# Numpad.net
KiCad netlist of a schematic drawn in EAGLE
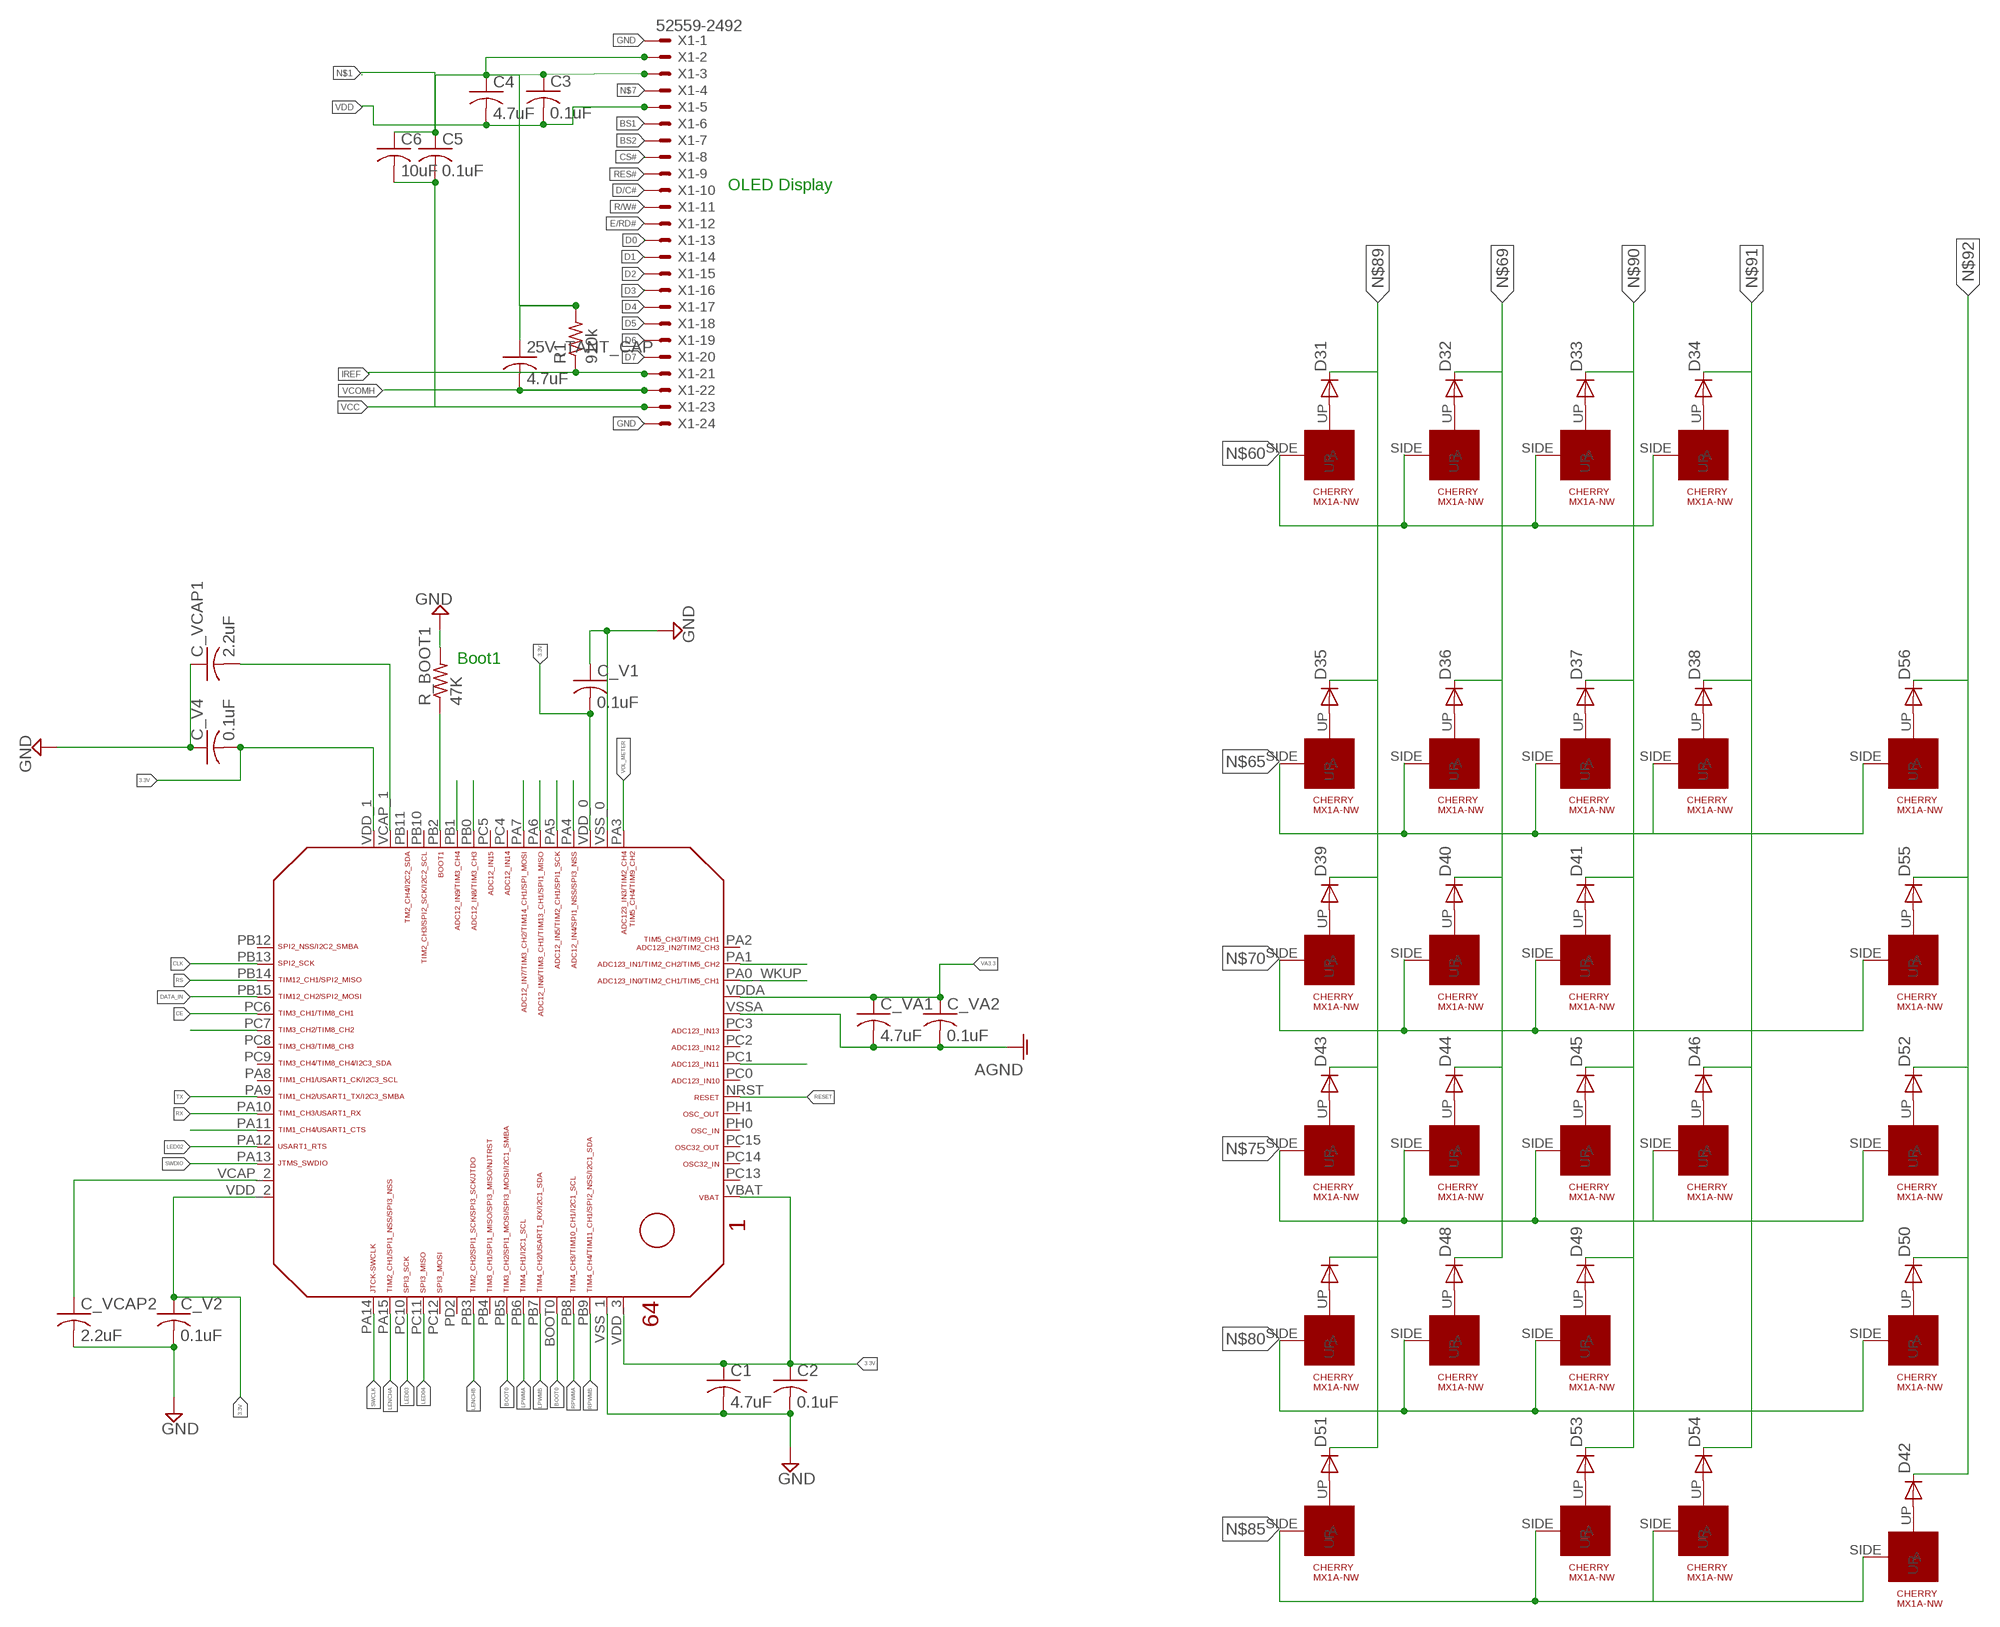
[diagram p0: schematic, sheet 1]

(export (version "E")
  (design (tool "Eeschema 10.0.6"))
  (components
    (comp (ref "25V_TANT_CAP")
      (value "4.7uF")
      (footprint "eagle-import:C0805")
      (libsource (lib "eagle-import") (part "C-USC0805"))
    )
    (comp (ref "C1")
      (value "4.7uF")
      (footprint "eagle-import:C0603")
      (libsource (lib "eagle-import") (part "resistor_348_C-USC0603"))
    )
    (comp (ref "C2")
      (value "0.1uF")
      (footprint "eagle-import:C0603")
      (libsource (lib "eagle-import") (part "resistor_348_C-USC0603"))
    )
    (comp (ref "C3")
      (value "0.1uF")
      (footprint "eagle-import:C0603")
      (libsource (lib "eagle-import") (part "resistor_348_C-USC0603"))
    )
    (comp (ref "C4")
      (value "4.7uF")
      (footprint "eagle-import:C0603")
      (libsource (lib "eagle-import") (part "resistor_348_C-USC0603"))
    )
    (comp (ref "C5")
      (value "0.1uF")
      (footprint "eagle-import:C0603")
      (libsource (lib "eagle-import") (part "resistor_348_C-USC0603"))
    )
    (comp (ref "C6")
      (value "10uF")
      (footprint "eagle-import:C0603")
      (libsource (lib "eagle-import") (part "resistor_348_C-USC0603"))
    )
    (comp (ref "C_V1")
      (value "0.1uF")
      (footprint "eagle-import:C0603")
      (libsource (lib "eagle-import") (part "resistor_348_C-USC0603"))
    )
    (comp (ref "C_V2")
      (value "0.1uF")
      (footprint "eagle-import:C0603")
      (libsource (lib "eagle-import") (part "resistor_348_C-USC0603"))
    )
    (comp (ref "C_V4")
      (value "0.1uF")
      (footprint "eagle-import:C0603")
      (libsource (lib "eagle-import") (part "resistor_348_C-USC0603"))
    )
    (comp (ref "C_VA1")
      (value "4.7uF")
      (footprint "eagle-import:C0603")
      (libsource (lib "eagle-import") (part "resistor_348_C-USC0603"))
    )
    (comp (ref "C_VA2")
      (value "0.1uF")
      (footprint "eagle-import:C0603")
      (libsource (lib "eagle-import") (part "resistor_348_C-USC0603"))
    )
    (comp (ref "C_VCAP1")
      (value "2.2uF")
      (footprint "eagle-import:C0603")
      (libsource (lib "eagle-import") (part "resistor_348_C-USC0603"))
    )
    (comp (ref "C_VCAP2")
      (value "2.2uF")
      (footprint "eagle-import:C0603")
      (libsource (lib "eagle-import") (part "resistor_348_C-USC0603"))
    )
    (comp (ref "D31")
      (value "1N4148DO35-7")
      (footprint "eagle-import:DO35-7")
      (libsource (lib "eagle-import") (part "1N4148DO35-7"))
    )
    (comp (ref "D32")
      (value "1N4148DO35-7")
      (footprint "eagle-import:DO35-7")
      (libsource (lib "eagle-import") (part "1N4148DO35-7"))
    )
    (comp (ref "D33")
      (value "1N4148DO35-7")
      (footprint "eagle-import:DO35-7")
      (libsource (lib "eagle-import") (part "1N4148DO35-7"))
    )
    (comp (ref "D34")
      (value "1N4148DO35-7")
      (footprint "eagle-import:DO35-7")
      (libsource (lib "eagle-import") (part "1N4148DO35-7"))
    )
    (comp (ref "D35")
      (value "1N4148DO35-7")
      (footprint "eagle-import:DO35-7")
      (libsource (lib "eagle-import") (part "1N4148DO35-7"))
    )
    (comp (ref "D36")
      (value "1N4148DO35-7")
      (footprint "eagle-import:DO35-7")
      (libsource (lib "eagle-import") (part "1N4148DO35-7"))
    )
    (comp (ref "D37")
      (value "1N4148DO35-7")
      (footprint "eagle-import:DO35-7")
      (libsource (lib "eagle-import") (part "1N4148DO35-7"))
    )
    (comp (ref "D38")
      (value "1N4148DO35-7")
      (footprint "eagle-import:DO35-7")
      (libsource (lib "eagle-import") (part "1N4148DO35-7"))
    )
    (comp (ref "D39")
      (value "1N4148DO35-7")
      (footprint "eagle-import:DO35-7")
      (libsource (lib "eagle-import") (part "1N4148DO35-7"))
    )
    (comp (ref "D40")
      (value "1N4148DO35-7")
      (footprint "eagle-import:DO35-7")
      (libsource (lib "eagle-import") (part "1N4148DO35-7"))
    )
    (comp (ref "D41")
      (value "1N4148DO35-7")
      (footprint "eagle-import:DO35-7")
      (libsource (lib "eagle-import") (part "1N4148DO35-7"))
    )
    (comp (ref "D42")
      (value "1N4148DO35-7")
      (footprint "eagle-import:DO35-7")
      (libsource (lib "eagle-import") (part "1N4148DO35-7"))
    )
    (comp (ref "D43")
      (value "1N4148DO35-7")
      (footprint "eagle-import:DO35-7")
      (libsource (lib "eagle-import") (part "1N4148DO35-7"))
    )
    (comp (ref "D44")
      (value "1N4148DO35-7")
      (footprint "eagle-import:DO35-7")
      (libsource (lib "eagle-import") (part "1N4148DO35-7"))
    )
    (comp (ref "D45")
      (value "1N4148DO35-7")
      (footprint "eagle-import:DO35-7")
      (libsource (lib "eagle-import") (part "1N4148DO35-7"))
    )
    (comp (ref "D46")
      (value "1N4148DO35-7")
      (footprint "eagle-import:DO35-7")
      (libsource (lib "eagle-import") (part "1N4148DO35-7"))
    )
    (comp (ref "D47")
      (value "1N4148DO35-7")
      (footprint "eagle-import:DO35-7")
      (libsource (lib "eagle-import") (part "1N4148DO35-7"))
    )
    (comp (ref "D48")
      (value "1N4148DO35-7")
      (footprint "eagle-import:DO35-7")
      (libsource (lib "eagle-import") (part "1N4148DO35-7"))
    )
    (comp (ref "D49")
      (value "1N4148DO35-7")
      (footprint "eagle-import:DO35-7")
      (libsource (lib "eagle-import") (part "1N4148DO35-7"))
    )
    (comp (ref "D50")
      (value "1N4148DO35-7")
      (footprint "eagle-import:DO35-7")
      (libsource (lib "eagle-import") (part "1N4148DO35-7"))
    )
    (comp (ref "D51")
      (value "1N4148DO35-7")
      (footprint "eagle-import:DO35-7")
      (libsource (lib "eagle-import") (part "1N4148DO35-7"))
    )
    (comp (ref "D52")
      (value "1N4148DO35-7")
      (footprint "eagle-import:DO35-7")
      (libsource (lib "eagle-import") (part "1N4148DO35-7"))
    )
    (comp (ref "D53")
      (value "1N4148DO35-7")
      (footprint "eagle-import:DO35-7")
      (libsource (lib "eagle-import") (part "1N4148DO35-7"))
    )
    (comp (ref "D54")
      (value "1N4148DO35-7")
      (footprint "eagle-import:DO35-7")
      (libsource (lib "eagle-import") (part "1N4148DO35-7"))
    )
    (comp (ref "D55")
      (value "1N4148DO35-7")
      (footprint "eagle-import:DO35-7")
      (libsource (lib "eagle-import") (part "1N4148DO35-7"))
    )
    (comp (ref "D56")
      (value "1N4148DO35-7")
      (footprint "eagle-import:DO35-7")
      (libsource (lib "eagle-import") (part "1N4148DO35-7"))
    )
    (comp (ref "R1")
      (value "910k")
      (footprint "eagle-import:R0603")
      (libsource (lib "eagle-import") (part "R-US_R0603"))
    )
    (comp (ref "R_BOOT1")
      (value "47K")
      (footprint "eagle-import:R0603")
      (libsource (lib "eagle-import") (part "R-US_R0603"))
    )
    (comp (ref "U$31")
      (value "CHERRY-MX1A-E1NW")
      (footprint "eagle-import:CHERRYMX-NN")
      (libsource (lib "eagle-import") (part "CHERRY-MX1A-E1NW"))
    )
    (comp (ref "U$35")
      (value "STM32F405/415_LQFP64")
      (footprint "eagle-import:STM32F405_415_LQFP64")
      (libsource (lib "eagle-import") (part "STM32F405/415_LQFP64"))
    )
    (comp (ref "U$36")
      (value "CHERRY-MX1A-E1NW")
      (footprint "eagle-import:CHERRYMX-NN")
      (libsource (lib "eagle-import") (part "CHERRY-MX1A-E1NW"))
    )
    (comp (ref "U$37")
      (value "CHERRY-MX1A-E1NW")
      (footprint "eagle-import:CHERRYMX-NN")
      (libsource (lib "eagle-import") (part "CHERRY-MX1A-E1NW"))
    )
    (comp (ref "U$38")
      (value "CHERRY-MX1A-E1NW")
      (footprint "eagle-import:CHERRYMX-NN")
      (libsource (lib "eagle-import") (part "CHERRY-MX1A-E1NW"))
    )
    (comp (ref "U$39")
      (value "CHERRY-MX1A-E1NW")
      (footprint "eagle-import:CHERRYMX-NN")
      (libsource (lib "eagle-import") (part "CHERRY-MX1A-E1NW"))
    )
    (comp (ref "U$40")
      (value "CHERRY-MX1A-E1NW")
      (footprint "eagle-import:CHERRYMX-NN")
      (libsource (lib "eagle-import") (part "CHERRY-MX1A-E1NW"))
    )
    (comp (ref "U$41")
      (value "CHERRY-MX1A-E1NW")
      (footprint "eagle-import:CHERRYMX-NN")
      (libsource (lib "eagle-import") (part "CHERRY-MX1A-E1NW"))
    )
    (comp (ref "U$42")
      (value "CHERRY-MX1A-E1NW")
      (footprint "eagle-import:CHERRYMX-NN")
      (libsource (lib "eagle-import") (part "CHERRY-MX1A-E1NW"))
    )
    (comp (ref "U$43")
      (value "CHERRY-MX1A-E1NW")
      (footprint "eagle-import:CHERRYMX-NN")
      (libsource (lib "eagle-import") (part "CHERRY-MX1A-E1NW"))
    )
    (comp (ref "U$44")
      (value "CHERRY-MX1A-E1NW")
      (footprint "eagle-import:CHERRYMX-NN")
      (libsource (lib "eagle-import") (part "CHERRY-MX1A-E1NW"))
    )
    (comp (ref "U$45")
      (value "CHERRY-MX1A-E1NW")
      (footprint "eagle-import:CHERRYMX-NN")
      (libsource (lib "eagle-import") (part "CHERRY-MX1A-E1NW"))
    )
    (comp (ref "U$46")
      (value "CHERRY-MX1A-E1NW")
      (footprint "eagle-import:CHERRYMX-NN")
      (libsource (lib "eagle-import") (part "CHERRY-MX1A-E1NW"))
    )
    (comp (ref "U$47")
      (value "CHERRY-MX1A-E1NW")
      (footprint "eagle-import:CHERRYMX-NN")
      (libsource (lib "eagle-import") (part "CHERRY-MX1A-E1NW"))
    )
    (comp (ref "U$48")
      (value "CHERRY-MX1A-E1NW")
      (footprint "eagle-import:CHERRYMX-NN")
      (libsource (lib "eagle-import") (part "CHERRY-MX1A-E1NW"))
    )
    (comp (ref "U$49")
      (value "CHERRY-MX1A-E1NW")
      (footprint "eagle-import:CHERRYMX-NN")
      (libsource (lib "eagle-import") (part "CHERRY-MX1A-E1NW"))
    )
    (comp (ref "U$50")
      (value "CHERRY-MX1A-E1NW")
      (footprint "eagle-import:CHERRYMX-NN")
      (libsource (lib "eagle-import") (part "CHERRY-MX1A-E1NW"))
    )
    (comp (ref "U$51")
      (value "CHERRY-MX1A-E1NW")
      (footprint "eagle-import:CHERRYMX-NN")
      (libsource (lib "eagle-import") (part "CHERRY-MX1A-E1NW"))
    )
    (comp (ref "U$52")
      (value "CHERRY-MX1A-E1NW")
      (footprint "eagle-import:CHERRYMX-NN")
      (libsource (lib "eagle-import") (part "CHERRY-MX1A-E1NW"))
    )
    (comp (ref "U$53")
      (value "CHERRY-MX1A-E1NW")
      (footprint "eagle-import:CHERRYMX-NN")
      (libsource (lib "eagle-import") (part "CHERRY-MX1A-E1NW"))
    )
    (comp (ref "U$54")
      (value "CHERRY-MX1A-E1NW")
      (footprint "eagle-import:CHERRYMX-NN")
      (libsource (lib "eagle-import") (part "CHERRY-MX1A-E1NW"))
    )
    (comp (ref "U$55")
      (value "CHERRY-MX1A-E1NW")
      (footprint "eagle-import:CHERRYMX-NN")
      (libsource (lib "eagle-import") (part "CHERRY-MX1A-E1NW"))
    )
    (comp (ref "U$56")
      (value "CHERRY-MX1A-E1NW")
      (footprint "eagle-import:CHERRYMX-NN")
      (libsource (lib "eagle-import") (part "CHERRY-MX1A-E1NW"))
    )
    (comp (ref "U$57")
      (value "CHERRY-MX1A-E1NW")
      (footprint "eagle-import:CHERRYMX-NN")
      (libsource (lib "eagle-import") (part "CHERRY-MX1A-E1NW"))
    )
    (comp (ref "U$58")
      (value "CHERRY-MX1A-E1NW")
      (footprint "eagle-import:CHERRYMX-NN")
      (libsource (lib "eagle-import") (part "CHERRY-MX1A-E1NW"))
    )
    (comp (ref "U$59")
      (value "CHERRY-MX1A-E1NW")
      (footprint "eagle-import:CHERRYMX-NN")
      (libsource (lib "eagle-import") (part "CHERRY-MX1A-E1NW"))
    )
    (comp (ref "U$60")
      (value "CHERRY-MX1A-E1NW")
      (footprint "eagle-import:CHERRYMX-NN")
      (libsource (lib "eagle-import") (part "CHERRY-MX1A-E1NW"))
    )
    (comp (ref "X1")
      (value "52559-2492")
      (footprint "eagle-import:52559-2492")
      (fields (field (name "MF") "MOLEX"))
      (libsource (lib "eagle-import") (part "52559-2492"))
    )
  )
  (nets
    (net (code "1") (name "3.3V") (class "Default")
      (node (ref "C1") (pin "1") (pinfunction "1_1") (pintype "passive"))
      (node (ref "C2") (pin "1") (pinfunction "1_1") (pintype "passive"))
      (node (ref "C_V1") (pin "2") (pinfunction "2_2") (pintype "passive"))
      (node (ref "C_V2") (pin "1") (pinfunction "1_1") (pintype "passive"))
      (node (ref "C_V4") (pin "2") (pinfunction "2_2") (pintype "passive"))
      (node (ref "U$35") (pin "VBAT") (pinfunction "VBAT_VBAT") (pintype "bidirectional"))
      (node (ref "U$35") (pin "VDD_0") (pinfunction "VDD_0_VDD_0") (pintype "bidirectional"))
      (node (ref "U$35") (pin "VDD_1") (pinfunction "VDD_1_VDD_1") (pintype "bidirectional"))
      (node (ref "U$35") (pin "VDD_2") (pinfunction "VDD_2_VDD_2") (pintype "bidirectional"))
      (node (ref "U$35") (pin "VDD_3") (pinfunction "VDD_3_VDD_3") (pintype "bidirectional"))
    )
    (net (code "2") (name "AGND") (class "Default")
      (node (ref "C_VA1") (pin "2") (pinfunction "2_2") (pintype "passive"))
      (node (ref "C_VA2") (pin "2") (pinfunction "2_2") (pintype "passive"))
      (node (ref "U$35") (pin "VSSA") (pinfunction "VSSA_VSSA") (pintype "bidirectional"))
    )
    (net (code "3") (name "BOOT0") (class "Default")
      (node (ref "U$35") (pin "BOOT0") (pinfunction "BOOT0_BOOT0") (pintype "bidirectional"))
      (node (ref "U$35") (pin "PB5") (pinfunction "PB5_PB5") (pintype "bidirectional"))
    )
    (net (code "4") (name "BS1") (class "Default")
      (node (ref "X1") (pin "6") (pinfunction "S_6") (pintype "passive"))
    )
    (net (code "5") (name "BS2") (class "Default")
      (node (ref "X1") (pin "7") (pinfunction "S_7") (pintype "passive"))
    )
    (net (code "6") (name "CE") (class "Default")
      (node (ref "U$35") (pin "PC6") (pinfunction "PC6_PC6") (pintype "bidirectional"))
    )
    (net (code "7") (name "CLK") (class "Default")
      (node (ref "U$35") (pin "PB13") (pinfunction "PB13_PB13") (pintype "bidirectional"))
    )
    (net (code "8") (name "CS#") (class "Default")
      (node (ref "X1") (pin "8") (pinfunction "S_8") (pintype "passive"))
    )
    (net (code "9") (name "D0") (class "Default")
      (node (ref "X1") (pin "13") (pinfunction "S_13") (pintype "passive"))
    )
    (net (code "10") (name "D1") (class "Default")
      (node (ref "X1") (pin "14") (pinfunction "S_14") (pintype "passive"))
    )
    (net (code "11") (name "D2") (class "Default")
      (node (ref "X1") (pin "15") (pinfunction "S_15") (pintype "passive"))
    )
    (net (code "12") (name "D3") (class "Default")
      (node (ref "X1") (pin "16") (pinfunction "S_16") (pintype "passive"))
    )
    (net (code "13") (name "D4") (class "Default")
      (node (ref "X1") (pin "17") (pinfunction "S_17") (pintype "passive"))
    )
    (net (code "14") (name "D5") (class "Default")
      (node (ref "X1") (pin "18") (pinfunction "S_18") (pintype "passive"))
    )
    (net (code "15") (name "D6") (class "Default")
      (node (ref "X1") (pin "19") (pinfunction "S_19") (pintype "passive"))
    )
    (net (code "16") (name "D7") (class "Default")
      (node (ref "X1") (pin "20") (pinfunction "S_20") (pintype "passive"))
    )
    (net (code "17") (name "DATA_IN") (class "Default")
      (node (ref "U$35") (pin "PB15") (pinfunction "PB15_PB15") (pintype "bidirectional"))
    )
    (net (code "18") (name "D{slash}C#") (class "Default")
      (node (ref "X1") (pin "10") (pinfunction "S_10") (pintype "passive"))
    )
    (net (code "19") (name "E{slash}RD#") (class "Default")
      (node (ref "X1") (pin "12") (pinfunction "S_12") (pintype "passive"))
    )
    (net (code "20") (name "GND") (class "Default")
      (node (ref "C1") (pin "2") (pinfunction "2_2") (pintype "passive"))
      (node (ref "C2") (pin "2") (pinfunction "2_2") (pintype "passive"))
      (node (ref "C_V1") (pin "1") (pinfunction "1_1") (pintype "passive"))
      (node (ref "C_V2") (pin "2") (pinfunction "2_2") (pintype "passive"))
      (node (ref "C_V4") (pin "1") (pinfunction "1_1") (pintype "passive"))
      (node (ref "C_VCAP1") (pin "1") (pinfunction "1_1") (pintype "passive"))
      (node (ref "C_VCAP2") (pin "2") (pinfunction "2_2") (pintype "passive"))
      (node (ref "R_BOOT1") (pin "2") (pinfunction "2_2") (pintype "passive"))
      (node (ref "U$35") (pin "VSS_0") (pinfunction "VSS_0_VSS_0") (pintype "bidirectional"))
      (node (ref "U$35") (pin "VSS_1") (pinfunction "VSS_1_VSS_1") (pintype "bidirectional"))
      (node (ref "X1") (pin "1") (pinfunction "S_1") (pintype "passive"))
      (node (ref "X1") (pin "24") (pinfunction "S_24") (pintype "passive"))
    )
    (net (code "21") (name "IREF") (class "Default")
      (node (ref "R1") (pin "1") (pinfunction "1_1") (pintype "passive"))
      (node (ref "X1") (pin "21") (pinfunction "S_21") (pintype "passive"))
    )
    (net (code "22") (name "LED02") (class "Default")
      (node (ref "U$35") (pin "PA12") (pinfunction "PA12_PA12") (pintype "bidirectional"))
    )
    (net (code "23") (name "LED03") (class "Default")
      (node (ref "U$35") (pin "PC10") (pinfunction "PC10_PC10") (pintype "bidirectional"))
    )
    (net (code "24") (name "LED04") (class "Default")
      (node (ref "U$35") (pin "PC11") (pinfunction "PC11_PC11") (pintype "bidirectional"))
    )
    (net (code "25") (name "LENCHA") (class "Default")
      (node (ref "U$35") (pin "PA15") (pinfunction "PA15_PA15") (pintype "bidirectional"))
    )
    (net (code "26") (name "LENCHB") (class "Default")
      (node (ref "U$35") (pin "PB3") (pinfunction "PB3_PB3") (pintype "bidirectional"))
    )
    (net (code "27") (name "LPWMA") (class "Default")
      (node (ref "U$35") (pin "PB6") (pinfunction "PB6_PB6") (pintype "bidirectional"))
    )
    (net (code "28") (name "LPWMB") (class "Default")
      (node (ref "U$35") (pin "PB7") (pinfunction "PB7_PB7") (pintype "bidirectional"))
    )
    (net (code "30") (name "N$7") (class "Default")
      (node (ref "X1") (pin "4") (pinfunction "S_4") (pintype "passive"))
    )
    (net (code "31") (name "N$60") (class "Default")
      (node (ref "U$31") (pin "SIDE") (pinfunction "A_SIDE") (pintype "bidirectional"))
      (node (ref "U$36") (pin "SIDE") (pinfunction "A_SIDE") (pintype "bidirectional"))
      (node (ref "U$37") (pin "SIDE") (pinfunction "A_SIDE") (pintype "bidirectional"))
      (node (ref "U$38") (pin "SIDE") (pinfunction "A_SIDE") (pintype "bidirectional"))
    )
    (net (code "32") (name "N$65") (class "Default")
      (node (ref "U$39") (pin "SIDE") (pinfunction "A_SIDE") (pintype "bidirectional"))
      (node (ref "U$40") (pin "SIDE") (pinfunction "A_SIDE") (pintype "bidirectional"))
      (node (ref "U$41") (pin "SIDE") (pinfunction "A_SIDE") (pintype "bidirectional"))
      (node (ref "U$42") (pin "SIDE") (pinfunction "A_SIDE") (pintype "bidirectional"))
      (node (ref "U$60") (pin "SIDE") (pinfunction "A_SIDE") (pintype "bidirectional"))
    )
    (net (code "33") (name "N$69") (class "Default")
      (node (ref "D32") (pin "C") (pinfunction "C_C") (pintype "passive"))
      (node (ref "D36") (pin "C") (pinfunction "C_C") (pintype "passive"))
      (node (ref "D40") (pin "C") (pinfunction "C_C") (pintype "passive"))
      (node (ref "D44") (pin "C") (pinfunction "C_C") (pintype "passive"))
      (node (ref "D48") (pin "C") (pinfunction "C_C") (pintype "passive"))
    )
    (net (code "34") (name "N$70") (class "Default")
      (node (ref "U$43") (pin "SIDE") (pinfunction "A_SIDE") (pintype "bidirectional"))
      (node (ref "U$44") (pin "SIDE") (pinfunction "A_SIDE") (pintype "bidirectional"))
      (node (ref "U$45") (pin "SIDE") (pinfunction "A_SIDE") (pintype "bidirectional"))
      (node (ref "U$59") (pin "SIDE") (pinfunction "A_SIDE") (pintype "bidirectional"))
    )
    (net (code "35") (name "N$75") (class "Default")
      (node (ref "U$47") (pin "SIDE") (pinfunction "A_SIDE") (pintype "bidirectional"))
      (node (ref "U$48") (pin "SIDE") (pinfunction "A_SIDE") (pintype "bidirectional"))
      (node (ref "U$49") (pin "SIDE") (pinfunction "A_SIDE") (pintype "bidirectional"))
      (node (ref "U$50") (pin "SIDE") (pinfunction "A_SIDE") (pintype "bidirectional"))
      (node (ref "U$56") (pin "SIDE") (pinfunction "A_SIDE") (pintype "bidirectional"))
    )
    (net (code "36") (name "N$80") (class "Default")
      (node (ref "U$51") (pin "SIDE") (pinfunction "A_SIDE") (pintype "bidirectional"))
      (node (ref "U$52") (pin "SIDE") (pinfunction "A_SIDE") (pintype "bidirectional"))
      (node (ref "U$53") (pin "SIDE") (pinfunction "A_SIDE") (pintype "bidirectional"))
      (node (ref "U$54") (pin "SIDE") (pinfunction "A_SIDE") (pintype "bidirectional"))
    )
    (net (code "37") (name "N$85") (class "Default")
      (node (ref "U$46") (pin "SIDE") (pinfunction "A_SIDE") (pintype "bidirectional"))
      (node (ref "U$55") (pin "SIDE") (pinfunction "A_SIDE") (pintype "bidirectional"))
      (node (ref "U$57") (pin "SIDE") (pinfunction "A_SIDE") (pintype "bidirectional"))
      (node (ref "U$58") (pin "SIDE") (pinfunction "A_SIDE") (pintype "bidirectional"))
    )
    (net (code "38") (name "N$89") (class "Default")
      (node (ref "D31") (pin "C") (pinfunction "C_C") (pintype "passive"))
      (node (ref "D35") (pin "C") (pinfunction "C_C") (pintype "passive"))
      (node (ref "D39") (pin "C") (pinfunction "C_C") (pintype "passive"))
      (node (ref "D43") (pin "C") (pinfunction "C_C") (pintype "passive"))
      (node (ref "D47") (pin "C") (pinfunction "C_C") (pintype "passive"))
      (node (ref "D51") (pin "C") (pinfunction "C_C") (pintype "passive"))
    )
    (net (code "39") (name "N$90") (class "Default")
      (node (ref "D33") (pin "C") (pinfunction "C_C") (pintype "passive"))
      (node (ref "D37") (pin "C") (pinfunction "C_C") (pintype "passive"))
      (node (ref "D41") (pin "C") (pinfunction "C_C") (pintype "passive"))
      (node (ref "D45") (pin "C") (pinfunction "C_C") (pintype "passive"))
      (node (ref "D49") (pin "C") (pinfunction "C_C") (pintype "passive"))
      (node (ref "D53") (pin "C") (pinfunction "C_C") (pintype "passive"))
    )
    (net (code "40") (name "N$91") (class "Default")
      (node (ref "D34") (pin "C") (pinfunction "C_C") (pintype "passive"))
      (node (ref "D38") (pin "C") (pinfunction "C_C") (pintype "passive"))
      (node (ref "D46") (pin "C") (pinfunction "C_C") (pintype "passive"))
      (node (ref "D54") (pin "C") (pinfunction "C_C") (pintype "passive"))
    )
    (net (code "41") (name "N$92") (class "Default")
      (node (ref "D42") (pin "C") (pinfunction "C_C") (pintype "passive"))
      (node (ref "D50") (pin "C") (pinfunction "C_C") (pintype "passive"))
      (node (ref "D52") (pin "C") (pinfunction "C_C") (pintype "passive"))
      (node (ref "D55") (pin "C") (pinfunction "C_C") (pintype "passive"))
      (node (ref "D56") (pin "C") (pinfunction "C_C") (pintype "passive"))
    )
    (net (code "42") (name "Net-(C_VCAP1-Pad2)") (class "Default")
      (node (ref "C_VCAP1") (pin "2") (pinfunction "2_2") (pintype "passive"))
      (node (ref "U$35") (pin "VCAP_1") (pinfunction "VCAP_1_VCAP_1") (pintype "bidirectional"))
    )
    (net (code "43") (name "Net-(C_VCAP2-Pad1)") (class "Default")
      (node (ref "C_VCAP2") (pin "1") (pinfunction "1_1") (pintype "passive"))
      (node (ref "U$35") (pin "VCAP_2") (pinfunction "VCAP_2_VCAP_2") (pintype "bidirectional"))
    )
    (net (code "44") (name "Net-(D31-PadA)") (class "Default")
      (node (ref "D31") (pin "A") (pinfunction "A_A") (pintype "passive"))
      (node (ref "U$31") (pin "UP") (pinfunction "UP_UP") (pintype "bidirectional"))
    )
    (net (code "45") (name "Net-(D32-PadA)") (class "Default")
      (node (ref "D32") (pin "A") (pinfunction "A_A") (pintype "passive"))
      (node (ref "U$36") (pin "UP") (pinfunction "UP_UP") (pintype "bidirectional"))
    )
    (net (code "46") (name "Net-(D33-PadA)") (class "Default")
      (node (ref "D33") (pin "A") (pinfunction "A_A") (pintype "passive"))
      (node (ref "U$37") (pin "UP") (pinfunction "UP_UP") (pintype "bidirectional"))
    )
    (net (code "47") (name "Net-(D34-PadA)") (class "Default")
      (node (ref "D34") (pin "A") (pinfunction "A_A") (pintype "passive"))
      (node (ref "U$38") (pin "UP") (pinfunction "UP_UP") (pintype "bidirectional"))
    )
    (net (code "48") (name "Net-(D35-PadA)") (class "Default")
      (node (ref "D35") (pin "A") (pinfunction "A_A") (pintype "passive"))
      (node (ref "U$39") (pin "UP") (pinfunction "UP_UP") (pintype "bidirectional"))
    )
    (net (code "49") (name "Net-(D36-PadA)") (class "Default")
      (node (ref "D36") (pin "A") (pinfunction "A_A") (pintype "passive"))
      (node (ref "U$40") (pin "UP") (pinfunction "UP_UP") (pintype "bidirectional"))
    )
    (net (code "50") (name "Net-(D37-PadA)") (class "Default")
      (node (ref "D37") (pin "A") (pinfunction "A_A") (pintype "passive"))
      (node (ref "U$41") (pin "UP") (pinfunction "UP_UP") (pintype "bidirectional"))
    )
    (net (code "51") (name "Net-(D38-PadA)") (class "Default")
      (node (ref "D38") (pin "A") (pinfunction "A_A") (pintype "passive"))
      (node (ref "U$42") (pin "UP") (pinfunction "UP_UP") (pintype "bidirectional"))
    )
    (net (code "52") (name "Net-(D39-PadA)") (class "Default")
      (node (ref "D39") (pin "A") (pinfunction "A_A") (pintype "passive"))
      (node (ref "U$43") (pin "UP") (pinfunction "UP_UP") (pintype "bidirectional"))
    )
    (net (code "53") (name "Net-(D40-PadA)") (class "Default")
      (node (ref "D40") (pin "A") (pinfunction "A_A") (pintype "passive"))
      (node (ref "U$44") (pin "UP") (pinfunction "UP_UP") (pintype "bidirectional"))
    )
    (net (code "54") (name "Net-(D41-PadA)") (class "Default")
      (node (ref "D41") (pin "A") (pinfunction "A_A") (pintype "passive"))
      (node (ref "U$45") (pin "UP") (pinfunction "UP_UP") (pintype "bidirectional"))
    )
    (net (code "55") (name "Net-(D42-PadA)") (class "Default")
      (node (ref "D42") (pin "A") (pinfunction "A_A") (pintype "passive"))
      (node (ref "U$46") (pin "UP") (pinfunction "UP_UP") (pintype "bidirectional"))
    )
    (net (code "56") (name "Net-(D43-PadA)") (class "Default")
      (node (ref "D43") (pin "A") (pinfunction "A_A") (pintype "passive"))
      (node (ref "U$47") (pin "UP") (pinfunction "UP_UP") (pintype "bidirectional"))
    )
    (net (code "57") (name "Net-(D44-PadA)") (class "Default")
      (node (ref "D44") (pin "A") (pinfunction "A_A") (pintype "passive"))
      (node (ref "U$48") (pin "UP") (pinfunction "UP_UP") (pintype "bidirectional"))
    )
    (net (code "58") (name "Net-(D45-PadA)") (class "Default")
      (node (ref "D45") (pin "A") (pinfunction "A_A") (pintype "passive"))
      (node (ref "U$49") (pin "UP") (pinfunction "UP_UP") (pintype "bidirectional"))
    )
    (net (code "59") (name "Net-(D46-PadA)") (class "Default")
      (node (ref "D46") (pin "A") (pinfunction "A_A") (pintype "passive"))
      (node (ref "U$50") (pin "UP") (pinfunction "UP_UP") (pintype "bidirectional"))
    )
    (net (code "60") (name "Net-(D47-PadA)") (class "Default")
      (node (ref "D47") (pin "A") (pinfunction "A_A") (pintype "passive"))
      (node (ref "U$51") (pin "UP") (pinfunction "UP_UP") (pintype "bidirectional"))
    )
    (net (code "61") (name "Net-(D48-PadA)") (class "Default")
      (node (ref "D48") (pin "A") (pinfunction "A_A") (pintype "passive"))
      (node (ref "U$52") (pin "UP") (pinfunction "UP_UP") (pintype "bidirectional"))
    )
    (net (code "62") (name "Net-(D49-PadA)") (class "Default")
      (node (ref "D49") (pin "A") (pinfunction "A_A") (pintype "passive"))
      (node (ref "U$53") (pin "UP") (pinfunction "UP_UP") (pintype "bidirectional"))
    )
    (net (code "63") (name "Net-(D50-PadA)") (class "Default")
      (node (ref "D50") (pin "A") (pinfunction "A_A") (pintype "passive"))
      (node (ref "U$54") (pin "UP") (pinfunction "UP_UP") (pintype "bidirectional"))
    )
    (net (code "64") (name "Net-(D51-PadA)") (class "Default")
      (node (ref "D51") (pin "A") (pinfunction "A_A") (pintype "passive"))
      (node (ref "U$55") (pin "UP") (pinfunction "UP_UP") (pintype "bidirectional"))
    )
    (net (code "65") (name "Net-(D52-PadA)") (class "Default")
      (node (ref "D52") (pin "A") (pinfunction "A_A") (pintype "passive"))
      (node (ref "U$56") (pin "UP") (pinfunction "UP_UP") (pintype "bidirectional"))
    )
    (net (code "66") (name "Net-(D53-PadA)") (class "Default")
      (node (ref "D53") (pin "A") (pinfunction "A_A") (pintype "passive"))
      (node (ref "U$57") (pin "UP") (pinfunction "UP_UP") (pintype "bidirectional"))
    )
    (net (code "67") (name "Net-(D54-PadA)") (class "Default")
      (node (ref "D54") (pin "A") (pinfunction "A_A") (pintype "passive"))
      (node (ref "U$58") (pin "UP") (pinfunction "UP_UP") (pintype "bidirectional"))
    )
    (net (code "68") (name "Net-(D55-PadA)") (class "Default")
      (node (ref "D55") (pin "A") (pinfunction "A_A") (pintype "passive"))
      (node (ref "U$59") (pin "UP") (pinfunction "UP_UP") (pintype "bidirectional"))
    )
    (net (code "69") (name "Net-(D56-PadA)") (class "Default")
      (node (ref "D56") (pin "A") (pinfunction "A_A") (pintype "passive"))
      (node (ref "U$60") (pin "UP") (pinfunction "UP_UP") (pintype "bidirectional"))
    )
    (net (code "70") (name "Net-(R_BOOT1-Pad1)") (class "Default")
      (node (ref "R_BOOT1") (pin "1") (pinfunction "1_1") (pintype "passive"))
      (node (ref "U$35") (pin "PB2") (pinfunction "PB2_PB2") (pintype "bidirectional"))
    )
    (net (code "71") (name "Net-(X1L-S)") (class "Default")
      (node (ref "25V_TANT_CAP") (pin "1") (pinfunction "1_1") (pintype "passive"))
      (node (ref "C3") (pin "1") (pinfunction "1_1") (pintype "passive"))
      (node (ref "C4") (pin "1") (pinfunction "1_1") (pintype "passive"))
      (node (ref "C5") (pin "1") (pinfunction "1_1") (pintype "passive"))
      (node (ref "C6") (pin "1") (pinfunction "1_1") (pintype "passive"))
      (node (ref "R1") (pin "2") (pinfunction "2_2") (pintype "passive"))
      (node (ref "X1") (pin "2") (pinfunction "S_2") (pintype "passive"))
      (node (ref "X1") (pin "3") (pinfunction "S_3") (pintype "passive"))
    )
    (net (code "72") (name "RES#") (class "Default")
      (node (ref "X1") (pin "9") (pinfunction "S_9") (pintype "passive"))
    )
    (net (code "73") (name "RESET") (class "Default")
      (node (ref "U$35") (pin "NRST") (pinfunction "NRST_NRST") (pintype "bidirectional"))
    )
    (net (code "74") (name "RPWMA") (class "Default")
      (node (ref "U$35") (pin "PB8") (pinfunction "PB8_PB8") (pintype "bidirectional"))
    )
    (net (code "75") (name "RPWMB") (class "Default")
      (node (ref "U$35") (pin "PB9") (pinfunction "PB9_PB9") (pintype "bidirectional"))
    )
    (net (code "76") (name "RS") (class "Default")
      (node (ref "U$35") (pin "PB14") (pinfunction "PB14_PB14") (pintype "bidirectional"))
    )
    (net (code "77") (name "RX") (class "Default")
      (node (ref "U$35") (pin "PA10") (pinfunction "PA10_PA10") (pintype "bidirectional"))
    )
    (net (code "78") (name "R{slash}W#") (class "Default")
      (node (ref "X1") (pin "11") (pinfunction "S_11") (pintype "passive"))
    )
    (net (code "79") (name "SWCLK") (class "Default")
      (node (ref "U$35") (pin "PA14") (pinfunction "PA14_PA14") (pintype "bidirectional"))
    )
    (net (code "80") (name "SWDIO") (class "Default")
      (node (ref "U$35") (pin "PA13") (pinfunction "PA13_PA13") (pintype "bidirectional"))
    )
    (net (code "81") (name "TX") (class "Default")
      (node (ref "U$35") (pin "PA9") (pinfunction "PA9_PA9") (pintype "bidirectional"))
    )
    (net (code "82") (name "VA3.3") (class "Default")
      (node (ref "C_VA1") (pin "1") (pinfunction "1_1") (pintype "passive"))
      (node (ref "C_VA2") (pin "1") (pinfunction "1_1") (pintype "passive"))
      (node (ref "U$35") (pin "VDDA") (pinfunction "VDDA_VDDA") (pintype "bidirectional"))
    )
    (net (code "83") (name "VCC") (class "Default")
      (node (ref "C5") (pin "2") (pinfunction "2_2") (pintype "passive"))
      (node (ref "C6") (pin "2") (pinfunction "2_2") (pintype "passive"))
      (node (ref "X1") (pin "23") (pinfunction "S_23") (pintype "passive"))
    )
    (net (code "84") (name "VCOMH") (class "Default")
      (node (ref "25V_TANT_CAP") (pin "2") (pinfunction "2_2") (pintype "passive"))
      (node (ref "X1") (pin "22") (pinfunction "S_22") (pintype "passive"))
    )
    (net (code "85") (name "VDD") (class "Default")
      (node (ref "C3") (pin "2") (pinfunction "2_2") (pintype "passive"))
      (node (ref "C4") (pin "2") (pinfunction "2_2") (pintype "passive"))
      (node (ref "X1") (pin "5") (pinfunction "S_5") (pintype "passive"))
    )
    (net (code "86") (name "VOL_METER") (class "Default")
      (node (ref "U$35") (pin "PA3") (pinfunction "PA3_PA3") (pintype "bidirectional"))
    )
    (net (code "87") (name "unconnected-(U$35-PA0_AKUP-PadPA0_WKUP)") (class "Default")
      (node (ref "U$35") (pin "PA0_WKUP") (pinfunction "PA0_AKUP_PA0_WKUP") (pintype "bidirectional"))
    )
    (net (code "88") (name "unconnected-(U$35-PadPA1)") (class "Default")
      (node (ref "U$35") (pin "PA1") (pinfunction "PA1_PA1") (pintype "bidirectional"))
    )
    (net (code "89") (name "unconnected-(U$35-PadPA2)") (class "Default")
      (node (ref "U$35") (pin "PA2") (pinfunction "PA2_PA2") (pintype "bidirectional"))
    )
    (net (code "90") (name "unconnected-(U$35-PadPA4)") (class "Default")
      (node (ref "U$35") (pin "PA4") (pinfunction "PA4_PA4") (pintype "bidirectional"))
    )
    (net (code "91") (name "unconnected-(U$35-PadPA5)") (class "Default")
      (node (ref "U$35") (pin "PA5") (pinfunction "PA5_PA5") (pintype "bidirectional"))
    )
    (net (code "92") (name "unconnected-(U$35-PadPA6)") (class "Default")
      (node (ref "U$35") (pin "PA6") (pinfunction "PA6_PA6") (pintype "bidirectional"))
    )
    (net (code "93") (name "unconnected-(U$35-PadPA7)") (class "Default")
      (node (ref "U$35") (pin "PA7") (pinfunction "PA7_PA7") (pintype "bidirectional"))
    )
    (net (code "94") (name "unconnected-(U$35-PadPA8)") (class "Default")
      (node (ref "U$35") (pin "PA8") (pinfunction "PA8_PA8") (pintype "bidirectional"))
    )
    (net (code "95") (name "unconnected-(U$35-PadPA11)") (class "Default")
      (node (ref "U$35") (pin "PA11") (pinfunction "PA11_PA11") (pintype "bidirectional"))
    )
    (net (code "96") (name "unconnected-(U$35-PadPB0)") (class "Default")
      (node (ref "U$35") (pin "PB0") (pinfunction "PB0_PB0") (pintype "bidirectional"))
    )
    (net (code "97") (name "unconnected-(U$35-PadPB1)") (class "Default")
      (node (ref "U$35") (pin "PB1") (pinfunction "PB1_PB1") (pintype "bidirectional"))
    )
    (net (code "98") (name "unconnected-(U$35-PadPB4)") (class "Default")
      (node (ref "U$35") (pin "PB4") (pinfunction "PB4_PB4") (pintype "bidirectional"))
    )
    (net (code "99") (name "unconnected-(U$35-PadPB10)") (class "Default")
      (node (ref "U$35") (pin "PB10") (pinfunction "PB10_PB10") (pintype "bidirectional"))
    )
    (net (code "100") (name "unconnected-(U$35-PadPB11)") (class "Default")
      (node (ref "U$35") (pin "PB11") (pinfunction "PB11_PB11") (pintype "bidirectional"))
    )
    (net (code "101") (name "unconnected-(U$35-PadPB12)") (class "Default")
      (node (ref "U$35") (pin "PB12") (pinfunction "PB12_PB12") (pintype "bidirectional"))
    )
    (net (code "102") (name "unconnected-(U$35-PadPC0)") (class "Default")
      (node (ref "U$35") (pin "PC0") (pinfunction "PC0_PC0") (pintype "bidirectional"))
    )
    (net (code "103") (name "unconnected-(U$35-PadPC1)") (class "Default")
      (node (ref "U$35") (pin "PC1") (pinfunction "PC1_PC1") (pintype "bidirectional"))
    )
    (net (code "104") (name "unconnected-(U$35-PadPC2)") (class "Default")
      (node (ref "U$35") (pin "PC2") (pinfunction "PC2_PC2") (pintype "bidirectional"))
    )
    (net (code "105") (name "unconnected-(U$35-PadPC3)") (class "Default")
      (node (ref "U$35") (pin "PC3") (pinfunction "PC3_PC3") (pintype "bidirectional"))
    )
    (net (code "106") (name "unconnected-(U$35-PadPC4)") (class "Default")
      (node (ref "U$35") (pin "PC4") (pinfunction "PC4_PC4") (pintype "bidirectional"))
    )
    (net (code "107") (name "unconnected-(U$35-PadPC5)") (class "Default")
      (node (ref "U$35") (pin "PC5") (pinfunction "PC5_PC5") (pintype "bidirectional"))
    )
    (net (code "108") (name "unconnected-(U$35-PadPC7)") (class "Default")
      (node (ref "U$35") (pin "PC7") (pinfunction "PC7_PC7") (pintype "bidirectional"))
    )
    (net (code "109") (name "unconnected-(U$35-PadPC8)") (class "Default")
      (node (ref "U$35") (pin "PC8") (pinfunction "PC8_PC8") (pintype "bidirectional"))
    )
    (net (code "110") (name "unconnected-(U$35-PadPC9)") (class "Default")
      (node (ref "U$35") (pin "PC9") (pinfunction "PC9_PC9") (pintype "bidirectional"))
    )
    (net (code "111") (name "unconnected-(U$35-PadPC12)") (class "Default")
      (node (ref "U$35") (pin "PC12") (pinfunction "PC12_PC12") (pintype "bidirectional"))
    )
    (net (code "112") (name "unconnected-(U$35-PadPC13)") (class "Default")
      (node (ref "U$35") (pin "PC13") (pinfunction "PC13_PC13") (pintype "bidirectional"))
    )
    (net (code "113") (name "unconnected-(U$35-PadPC14)") (class "Default")
      (node (ref "U$35") (pin "PC14") (pinfunction "PC14_PC14") (pintype "bidirectional"))
    )
    (net (code "114") (name "unconnected-(U$35-PadPC15)") (class "Default")
      (node (ref "U$35") (pin "PC15") (pinfunction "PC15_PC15") (pintype "bidirectional"))
    )
    (net (code "115") (name "unconnected-(U$35-PadPD2)") (class "Default")
      (node (ref "U$35") (pin "PD2") (pinfunction "PD2_PD2") (pintype "bidirectional"))
    )
    (net (code "116") (name "unconnected-(U$35-PadPH0)") (class "Default")
      (node (ref "U$35") (pin "PH0") (pinfunction "PH0_PH0") (pintype "bidirectional"))
    )
    (net (code "117") (name "unconnected-(U$35-PadPH1)") (class "Default")
      (node (ref "U$35") (pin "PH1") (pinfunction "PH1_PH1") (pintype "bidirectional"))
    )
  )
)
